# supply.net
KiCad netlist of a schematic drawn in Altium Designer
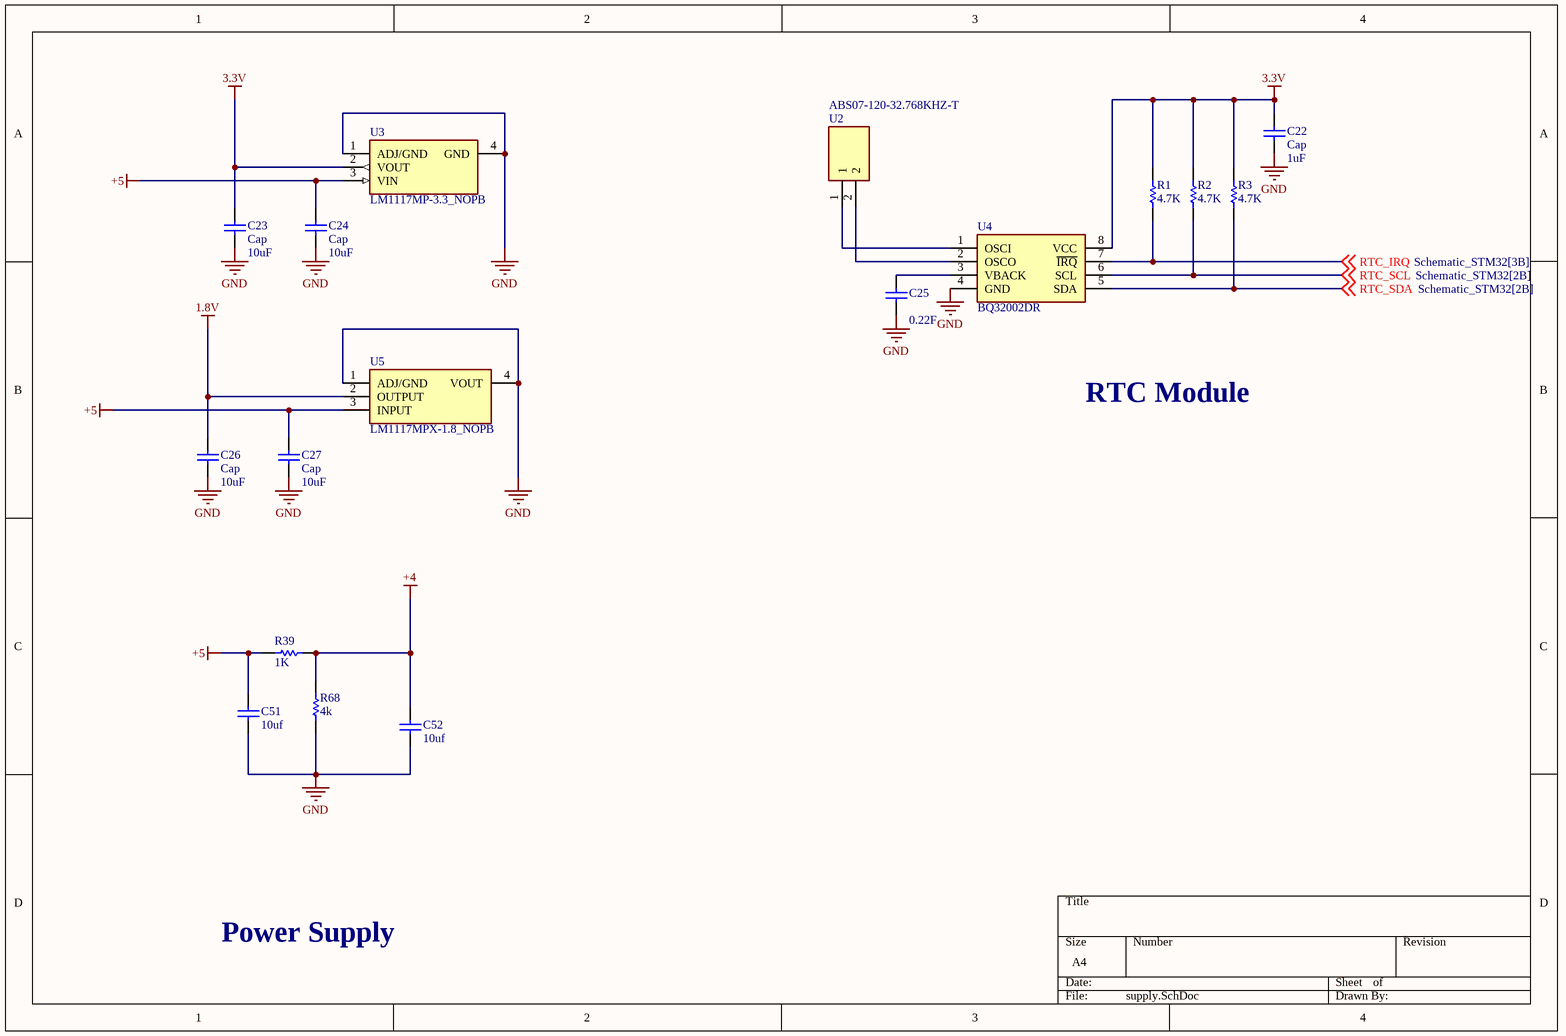
[diagram p0: supply.SchDoc]

(export (version "E")
  (design (tool "Eeschema 10.0.6"))
  (components
    (comp (ref "C22")
      (value "Cap")
      (footprint "RAD-0.3")
      (description "Capacitor")
      (fields (field (name "ALTIUM_VALUE") "1uF") (field (name "PUBLISHER") "Altium Limited"))
      (libsource (lib "Miscellaneous Devices") (part "Cap"))
    )
    (comp (ref "C23")
      (value "Cap")
      (footprint "RAD-0.3")
      (description "Capacitor")
      (fields (field (name "ALTIUM_VALUE") "10uF") (field (name "PUBLISHER") "Altium Limited"))
      (libsource (lib "Miscellaneous Devices") (part "Cap"))
    )
    (comp (ref "C24")
      (value "Cap")
      (footprint "RAD-0.3")
      (description "Capacitor")
      (fields (field (name "ALTIUM_VALUE") "10uF") (field (name "PUBLISHER") "Altium Limited"))
      (libsource (lib "Miscellaneous Devices") (part "Cap"))
    )
    (comp (ref "C25")
      (value "0.22F")
      (footprint "RAD-0.3")
      (description "Capacitor")
      (fields (field (name "Comment") "Cap") (field (name "PUBLISHER") "Altium Limited"))
      (libsource (lib "Miscellaneous Devices") (part "Cap"))
    )
    (comp (ref "C26")
      (value "Cap")
      (footprint "RAD-0.3")
      (description "Capacitor")
      (fields (field (name "ALTIUM_VALUE") "10uF") (field (name "PUBLISHER") "Altium Limited"))
      (libsource (lib "Miscellaneous Devices") (part "Cap"))
    )
    (comp (ref "C27")
      (value "Cap")
      (footprint "RAD-0.3")
      (description "Capacitor")
      (fields (field (name "ALTIUM_VALUE") "10uF") (field (name "PUBLISHER") "Altium Limited"))
      (libsource (lib "Miscellaneous Devices") (part "Cap"))
    )
    (comp (ref "C51")
      (value "10uf")
      (description "Capacitor")
      (libsource (lib "Simulation Generic Components") (part "Capacitor"))
    )
    (comp (ref "C52")
      (value "10uf")
      (description "Capacitor")
      (libsource (lib "Simulation Generic Components") (part "Capacitor"))
    )
    (comp (ref "R1")
      (value "4.7K")
      (footprint "AXIAL-0.3")
      (description "Resistor")
      (fields (field (name "Comment") "Res1") (field (name "PUBLISHER") "Altium Limited"))
      (libsource (lib "Miscellaneous Devices") (part "Res1"))
    )
    (comp (ref "R2")
      (value "4.7K")
      (footprint "AXIAL-0.3")
      (description "Resistor")
      (fields (field (name "Comment") "Res1") (field (name "PUBLISHER") "Altium Limited"))
      (libsource (lib "Miscellaneous Devices") (part "Res1"))
    )
    (comp (ref "R3")
      (value "4.7K")
      (footprint "AXIAL-0.3")
      (description "Resistor")
      (fields (field (name "Comment") "Res1") (field (name "PUBLISHER") "Altium Limited"))
      (libsource (lib "Miscellaneous Devices") (part "Res1"))
    )
    (comp (ref "R39")
      (value "1K")
      (description "Resistor")
      (libsource (lib "Simulation Generic Components") (part "Resistor"))
    )
    (comp (ref "R68")
      (value "4k")
      (description "Resistor")
      (libsource (lib "Simulation Generic Components") (part "Resistor"))
    )
    (comp (ref "U2")
      (value "ABS07-120-32.768KHZ-T")
      (footprint "SamacSys:ABS-07")
      (description "Crystal or Oscillator")
      (fields
        (field (name "MOUSER PART NUMBER") "815-ABS0712032.768KT")
        (field (name "RS PART NUMBER") "1712688P")
      )
      (libsource (lib "*") (part "ABS07-120-32.768KHZ-T"))
    )
    (comp (ref "U3")
      (value "LM1117MP-3.3_NOPB")
      (footprint "SamacSys:SOT230P700X180-4N")
      (description "Integrated Circuit")
      (fields
        (field (name "MANUFACTURER_PART_NUMBER") "LM1117MP-3.3/NOPB")
        (field (name "MOUSER PART NUMBER") "926-LM1117MP-3.3NOPB")
      )
      (libsource (lib "*") (part "LM1117MP-3.3_NOPB"))
    )
    (comp (ref "U4")
      (value "BQ32002DR")
      (footprint "SamacSys:SOIC127P600X175-8N")
      (description "Integrated Circuit")
      (fields (field (name "MOUSER PART NUMBER") "595-BQ32002DR"))
      (libsource (lib "*") (part "BQ32002DR"))
    )
    (comp (ref "U5")
      (value "LM1117MPX-1.8_NOPB")
      (footprint "SamacSys:SOT230P700X180-4N")
      (description "Integrated Circuit")
      (fields
        (field (name "MANUFACTURER_PART_NUMBER") "LM1117MPX-1.8/NOPB")
        (field (name "MOUSER PART NUMBER") "926-LM1117MPX1.8NOPB")
      )
      (libsource (lib "*") (part "LM1117MPX-1.8_NOPB"))
    )
  )
  (nets
    (net (code "1") (name "+4") (class "Default")
      (node (ref "C52") (pin "2") (pinfunction "2_2") (pintype "passive"))
      (node (ref "R39") (pin "2") (pinfunction "2_2") (pintype "passive"))
      (node (ref "R68") (pin "2") (pinfunction "2_2") (pintype "passive"))
    )
    (net (code "2") (name "+5") (class "Default")
      (node (ref "C24") (pin "2") (pinfunction "2_2") (pintype "passive"))
      (node (ref "C27") (pin "2") (pinfunction "2_2") (pintype "passive"))
      (node (ref "C51") (pin "2") (pinfunction "2_2") (pintype "passive"))
      (node (ref "R39") (pin "1") (pinfunction "1_1") (pintype "passive"))
      (node (ref "U3") (pin "3") (pinfunction "VIN_3") (pintype "input"))
      (node (ref "U5") (pin "3") (pinfunction "INPUT_3") (pintype "passive"))
    )
    (net (code "3") (name "1.8V") (class "Default")
      (node (ref "C26") (pin "2") (pinfunction "2_2") (pintype "passive"))
      (node (ref "U5") (pin "2") (pinfunction "OUTPUT_2") (pintype "passive"))
    )
    (net (code "4") (name "3.3V") (class "Default")
      (node (ref "C22") (pin "2") (pinfunction "2_2") (pintype "passive"))
      (node (ref "C23") (pin "2") (pinfunction "2_2") (pintype "passive"))
      (node (ref "R1") (pin "1") (pinfunction "1_1") (pintype "passive"))
      (node (ref "R2") (pin "1") (pinfunction "1_1") (pintype "passive"))
      (node (ref "R3") (pin "1") (pinfunction "1_1") (pintype "passive"))
      (node (ref "U3") (pin "2") (pinfunction "VOUT_2") (pintype "output"))
      (node (ref "U4") (pin "8") (pinfunction "VCC_8") (pintype "passive"))
    )
    (net (code "5") (name "GND") (class "Default")
      (node (ref "C22") (pin "1") (pinfunction "1_1") (pintype "passive"))
      (node (ref "C23") (pin "1") (pinfunction "1_1") (pintype "passive"))
      (node (ref "C24") (pin "1") (pinfunction "1_1") (pintype "passive"))
      (node (ref "C25") (pin "1") (pinfunction "1_1") (pintype "passive"))
      (node (ref "C26") (pin "1") (pinfunction "1_1") (pintype "passive"))
      (node (ref "C27") (pin "1") (pinfunction "1_1") (pintype "passive"))
      (node (ref "C51") (pin "1") (pinfunction "1_1") (pintype "passive"))
      (node (ref "C52") (pin "1") (pinfunction "1_1") (pintype "passive"))
      (node (ref "R68") (pin "1") (pinfunction "1_1") (pintype "passive"))
      (node (ref "U3") (pin "1") (pinfunction "ADJ/GND_1") (pintype "passive"))
      (node (ref "U3") (pin "4") (pinfunction "GND_4") (pintype "power_in"))
      (node (ref "U4") (pin "4") (pinfunction "GND_4") (pintype "passive"))
      (node (ref "U5") (pin "1") (pinfunction "ADJ/GND_1") (pintype "passive"))
      (node (ref "U5") (pin "4") (pinfunction "VOUT_4") (pintype "passive"))
    )
    (net (code "6") (name "Net-(U4-OSCI)") (class "Default")
      (node (ref "U2") (pin "1") (pinfunction "1_1") (pintype "passive"))
      (node (ref "U4") (pin "1") (pinfunction "OSCI_1") (pintype "passive"))
    )
    (net (code "7") (name "Net-(U4-OSCO)") (class "Default")
      (node (ref "U2") (pin "2") (pinfunction "2_2") (pintype "passive"))
      (node (ref "U4") (pin "2") (pinfunction "OSCO_2") (pintype "passive"))
    )
    (net (code "8") (name "Net-(U4-VBACK)") (class "Default")
      (node (ref "C25") (pin "2") (pinfunction "2_2") (pintype "passive"))
      (node (ref "U4") (pin "3") (pinfunction "VBACK_3") (pintype "passive"))
    )
    (net (code "9") (name "RTC_IRQ") (class "Default")
      (node (ref "R1") (pin "2") (pinfunction "2_2") (pintype "passive"))
      (node (ref "U4") (pin "7") (pinfunction "~{IRQ}_7") (pintype "passive"))
    )
    (net (code "10") (name "RTC_SCL") (class "Default")
      (node (ref "R2") (pin "2") (pinfunction "2_2") (pintype "passive"))
      (node (ref "U4") (pin "6") (pinfunction "SCL_6") (pintype "passive"))
    )
    (net (code "11") (name "RTC_SDA") (class "Default")
      (node (ref "R3") (pin "2") (pinfunction "2_2") (pintype "passive"))
      (node (ref "U4") (pin "5") (pinfunction "SDA_5") (pintype "passive"))
    )
  )
)
